# Audio2Trig.net
KiCad netlist of a schematic drawn in EAGLE
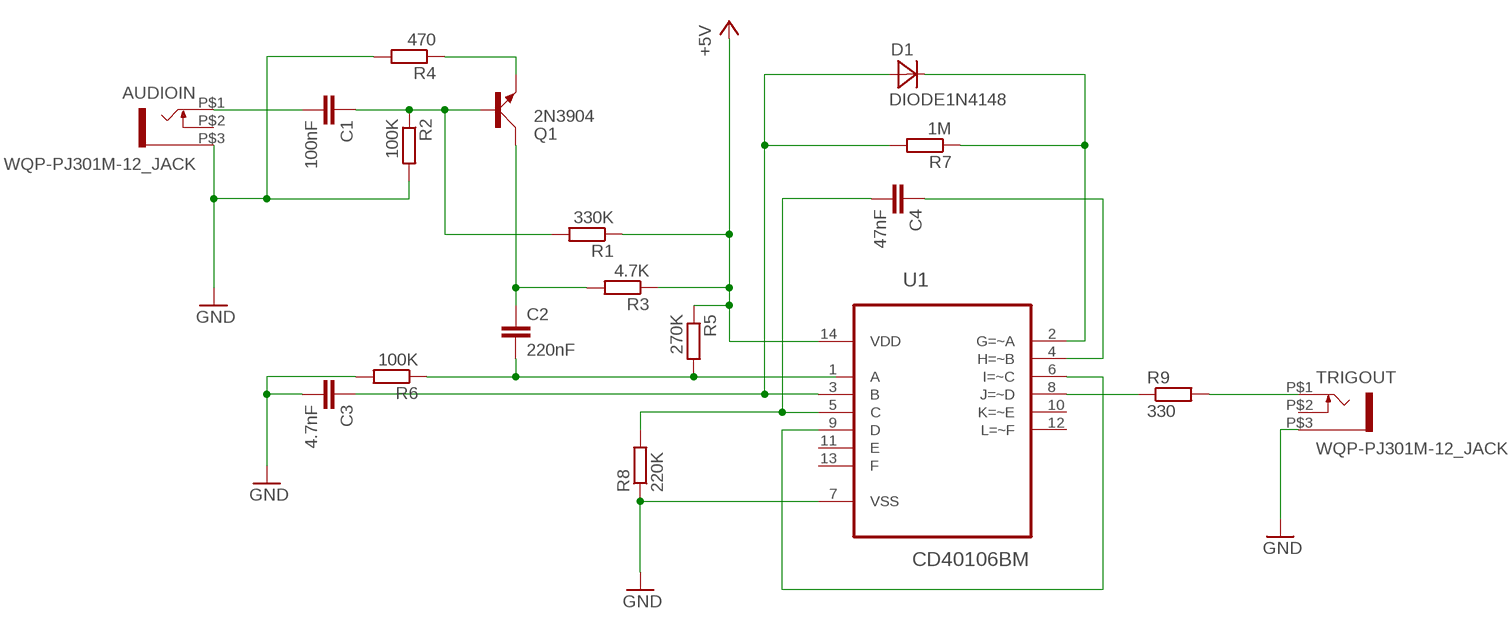
[diagram p0: schematic, sheet 1]

(export (version "E")
  (design (tool "Eeschema 10.0.6"))
  (components
    (comp (ref "AUDIOIN")
      (value "WQP-PJ301M-12_JACK")
      (footprint "eagle-import:WQP-PJ301M-12_JACK")
      (libsource (lib "eagle-import") (part "WQP-PJ301M-12_JACK"))
    )
    (comp (ref "C1")
      (value "100nF")
      (footprint "eagle-import:C025-025X050")
      (libsource (lib "eagle-import") (part "C-EU025-025X050"))
    )
    (comp (ref "C2")
      (value "220nF")
      (footprint "eagle-import:C025-025X050")
      (libsource (lib "eagle-import") (part "C-EU025-025X050"))
    )
    (comp (ref "C3")
      (value "4.7nF")
      (footprint "eagle-import:C025-025X050")
      (libsource (lib "eagle-import") (part "C-EU025-025X050"))
    )
    (comp (ref "C4")
      (value "47nF")
      (footprint "eagle-import:C025-025X050")
      (libsource (lib "eagle-import") (part "C-EU025-025X050"))
    )
    (comp (ref "D1")
      (value "DIODE1N4148")
      (footprint "eagle-import:DO-35")
      (libsource (lib "eagle-import") (part "DIODE1N4148"))
    )
    (comp (ref "Q1")
      (value "2N3904")
      (footprint "eagle-import:TO92D")
      (libsource (lib "eagle-import") (part "2N3904"))
    )
    (comp (ref "R1")
      (value "330K")
      (footprint "eagle-import:0204V")
      (libsource (lib "eagle-import") (part "R-EU_0204/2V"))
    )
    (comp (ref "R2")
      (value "100K")
      (footprint "eagle-import:0204V")
      (libsource (lib "eagle-import") (part "R-EU_0204/2V"))
    )
    (comp (ref "R3")
      (value "4.7K")
      (footprint "eagle-import:0204V")
      (libsource (lib "eagle-import") (part "R-EU_0204/2V"))
    )
    (comp (ref "R4")
      (value "470")
      (footprint "eagle-import:0204V")
      (libsource (lib "eagle-import") (part "R-EU_0204/2V"))
    )
    (comp (ref "R5")
      (value "270K")
      (footprint "eagle-import:0204V")
      (libsource (lib "eagle-import") (part "R-EU_0204/2V"))
    )
    (comp (ref "R6")
      (value "100K")
      (footprint "eagle-import:0204V")
      (libsource (lib "eagle-import") (part "R-EU_0204/2V"))
    )
    (comp (ref "R7")
      (value "1M")
      (footprint "eagle-import:0204V")
      (libsource (lib "eagle-import") (part "R-EU_0204/2V"))
    )
    (comp (ref "R8")
      (value "220K")
      (footprint "eagle-import:0204V")
      (libsource (lib "eagle-import") (part "R-EU_0204/2V"))
    )
    (comp (ref "R9")
      (value "330")
      (footprint "eagle-import:0204V")
      (libsource (lib "eagle-import") (part "R-EU_0204/2V"))
    )
    (comp (ref "TRIGOUT")
      (value "WQP-PJ301M-12_JACK")
      (footprint "eagle-import:WQP-PJ301M-12_JACK")
      (libsource (lib "eagle-import") (part "WQP-PJ301M-12_JACK"))
    )
    (comp (ref "U1")
      (value "CD40106BM")
      (footprint "eagle-import:SOIC127P600X175-14N")
      (libsource (lib "eagle-import") (part "CD40106BM"))
    )
  )
  (nets
    (net (code "1") (name "+5V") (class "Default")
      (node (ref "R1") (pin "1") (pinfunction "1_1") (pintype "passive"))
      (node (ref "R3") (pin "1") (pinfunction "1_1") (pintype "passive"))
      (node (ref "R5") (pin "1") (pinfunction "1_1") (pintype "passive"))
      (node (ref "U1") (pin "14") (pinfunction "VDD_14") (pintype "power_in"))
    )
    (net (code "2") (name "GND") (class "Default")
      (node (ref "AUDIOIN") (pin "P$3") (pinfunction "1_P$3") (pintype "passive"))
      (node (ref "C3") (pin "2") (pinfunction "2_2") (pintype "passive"))
      (node (ref "R2") (pin "2") (pinfunction "2_2") (pintype "passive"))
      (node (ref "R4") (pin "2") (pinfunction "2_2") (pintype "passive"))
      (node (ref "R6") (pin "2") (pinfunction "2_2") (pintype "passive"))
      (node (ref "R8") (pin "1") (pinfunction "1_1") (pintype "passive"))
      (node (ref "TRIGOUT") (pin "P$3") (pinfunction "1_P$3") (pintype "passive"))
      (node (ref "U1") (pin "7") (pinfunction "VSS_7") (pintype "power_in"))
    )
    (net (code "3") (name "Net-(AUDIOIN-2)") (class "Default")
      (node (ref "AUDIOIN") (pin "P$1") (pinfunction "2_P$1") (pintype "passive"))
      (node (ref "C1") (pin "2") (pinfunction "2_2") (pintype "passive"))
    )
    (net (code "4") (name "Net-(C1-Pad1)") (class "Default")
      (node (ref "C1") (pin "1") (pinfunction "1_1") (pintype "passive"))
      (node (ref "Q1") (pin "B") (pinfunction "B_B") (pintype "passive"))
      (node (ref "R1") (pin "2") (pinfunction "2_2") (pintype "passive"))
      (node (ref "R2") (pin "1") (pinfunction "1_1") (pintype "passive"))
    )
    (net (code "5") (name "Net-(C2-Pad1)") (class "Default")
      (node (ref "C2") (pin "1") (pinfunction "1_1") (pintype "passive"))
      (node (ref "Q1") (pin "C") (pinfunction "C_C") (pintype "passive"))
      (node (ref "R3") (pin "2") (pinfunction "2_2") (pintype "passive"))
    )
    (net (code "6") (name "Net-(C2-Pad2)") (class "Default")
      (node (ref "C2") (pin "2") (pinfunction "2_2") (pintype "passive"))
      (node (ref "R5") (pin "2") (pinfunction "2_2") (pintype "passive"))
      (node (ref "R6") (pin "1") (pinfunction "1_1") (pintype "passive"))
    )
    (net (code "7") (name "Net-(Q1-PadE)") (class "Default")
      (node (ref "Q1") (pin "E") (pinfunction "E_E") (pintype "passive"))
      (node (ref "R4") (pin "1") (pinfunction "1_1") (pintype "passive"))
    )
    (net (code "8") (name "Net-(TRIGOUT-2)") (class "Default")
      (node (ref "R9") (pin "2") (pinfunction "2_2") (pintype "passive"))
      (node (ref "TRIGOUT") (pin "P$1") (pinfunction "2_P$1") (pintype "passive"))
    )
    (net (code "9") (name "Net-(U1-B)") (class "Default")
      (node (ref "C3") (pin "1") (pinfunction "1_1") (pintype "passive"))
      (node (ref "D1") (pin "+") (pinfunction "+_+") (pintype "passive"))
      (node (ref "R7") (pin "2") (pinfunction "2_2") (pintype "passive"))
      (node (ref "U1") (pin "3") (pinfunction "B_3") (pintype "input"))
    )
    (net (code "10") (name "Net-(U1-C)") (class "Default")
      (node (ref "C4") (pin "2") (pinfunction "2_2") (pintype "passive"))
      (node (ref "R8") (pin "2") (pinfunction "2_2") (pintype "passive"))
      (node (ref "U1") (pin "5") (pinfunction "C_5") (pintype "input"))
    )
    (net (code "11") (name "Net-(U1-D)") (class "Default")
      (node (ref "U1") (pin "6") (pinfunction "I=~{C}_6") (pintype "output"))
      (node (ref "U1") (pin "9") (pinfunction "D_9") (pintype "input"))
    )
    (net (code "12") (name "Net-(U1-G=~{A})") (class "Default")
      (node (ref "D1") (pin "-") (pinfunction "-_-") (pintype "passive"))
      (node (ref "R7") (pin "1") (pinfunction "1_1") (pintype "passive"))
      (node (ref "U1") (pin "2") (pinfunction "G=~{A}_2") (pintype "output"))
    )
    (net (code "13") (name "Net-(U1-H=~{B})") (class "Default")
      (node (ref "C4") (pin "1") (pinfunction "1_1") (pintype "passive"))
      (node (ref "U1") (pin "4") (pinfunction "H=~{B}_4") (pintype "output"))
    )
    (net (code "14") (name "Net-(U1-J=~{D})") (class "Default")
      (node (ref "R9") (pin "1") (pinfunction "1_1") (pintype "passive"))
      (node (ref "U1") (pin "8") (pinfunction "J=~{D}_8") (pintype "output"))
    )
    (net (code "15") (name "unconnected-(AUDIOIN-3-PadP$2)") (class "Default")
      (node (ref "AUDIOIN") (pin "P$2") (pinfunction "3_P$2") (pintype "passive"))
    )
    (net (code "16") (name "unconnected-(TRIGOUT-3-PadP$2)") (class "Default")
      (node (ref "TRIGOUT") (pin "P$2") (pinfunction "3_P$2") (pintype "passive"))
    )
    (net (code "17") (name "unconnected-(U1-A-Pad1)") (class "Default")
      (node (ref "U1") (pin "1") (pinfunction "A_1") (pintype "input"))
    )
    (net (code "18") (name "unconnected-(U1-E-Pad11)") (class "Default")
      (node (ref "U1") (pin "11") (pinfunction "E_11") (pintype "input"))
    )
    (net (code "19") (name "unconnected-(U1-F-Pad13)") (class "Default")
      (node (ref "U1") (pin "13") (pinfunction "F_13") (pintype "input"))
    )
    (net (code "20") (name "unconnected-(U1-K=~{E}-Pad10)") (class "Default")
      (node (ref "U1") (pin "10") (pinfunction "K=~{E}_10") (pintype "output"))
    )
    (net (code "21") (name "unconnected-(U1-L=~{F}-Pad12)") (class "Default")
      (node (ref "U1") (pin "12") (pinfunction "L=~{F}_12") (pintype "output"))
    )
  )
)
